# FDC.net
KiCad netlist of a schematic drawn in Altium Designer
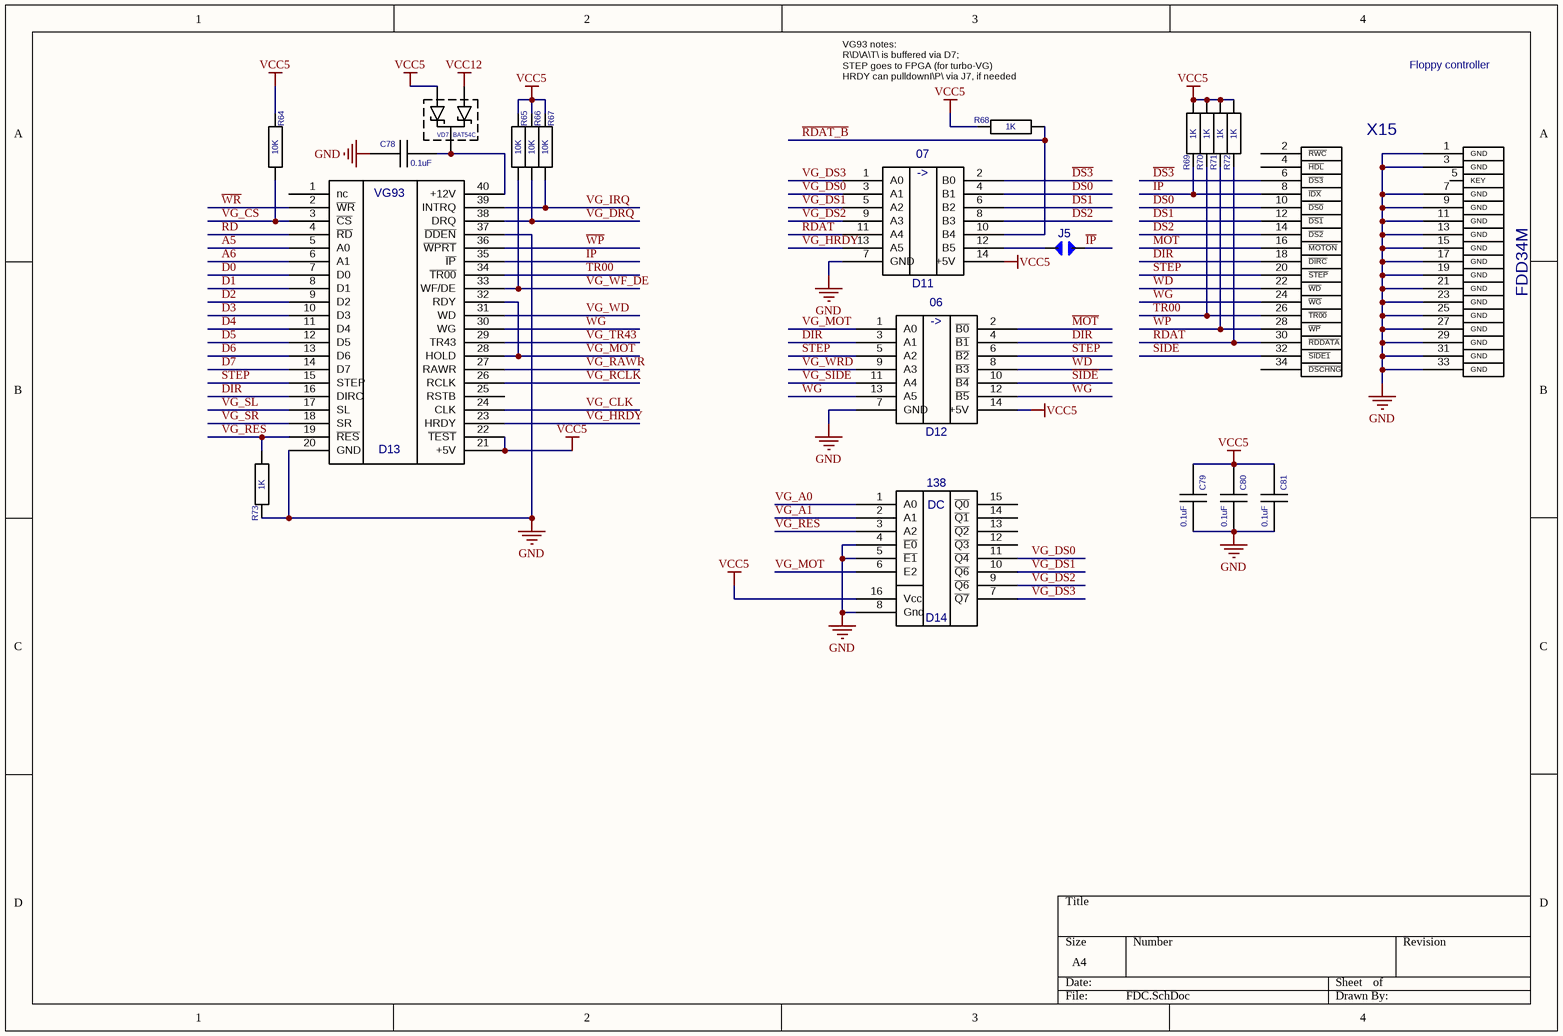
[diagram p0: FDC.SchDoc]

(export (version "E")
  (design (tool "Eeschema 10.0.6"))
  (components
    (comp (ref "C78")
      (value "0.1uF")
      (footprint "C-CHIP")
      (description "CAPCHIP")
      (libsource (lib "*") (part "CAPCHIP"))
    )
    (comp (ref "C79")
      (value "0.1uF")
      (footprint "C-CHIP")
      (description "CAPCHIP")
      (libsource (lib "*") (part "CAPCHIP"))
    )
    (comp (ref "C80")
      (value "0.1uF")
      (footprint "C-CHIP")
      (description "CAPCHIP")
      (libsource (lib "*") (part "CAPCHIP"))
    )
    (comp (ref "C81")
      (value "0.1uF")
      (footprint "C-CHIP")
      (description "CAPCHIP")
      (libsource (lib "*") (part "CAPCHIP"))
    )
    (comp (ref "D11") (value "07") (footprint "SO14") (libsource (lib "*") (part "07")))
    (comp (ref "D12") (value "06") (footprint "SO14") (libsource (lib "*") (part "06")))
    (comp (ref "D13") (value "KR1818VG93") (footprint "DIP40") (libsource (lib "*") (part "KR1818VG93")))
    (comp (ref "D14") (value "138") (footprint "SO16") (libsource (lib "*") (part "138")))
    (comp (ref "J5")
      (value "JUMPER")
      (footprint "JUMPER")
      (description "HLT->~IP")
      (libsource (lib "*") (part "JUMPER"))
    )
    (comp (ref "R64")
      (value "10K")
      (footprint "R-CHIP")
      (description "RESCHIP")
      (libsource (lib "*") (part "RESCHIP"))
    )
    (comp (ref "R65")
      (value "10K")
      (footprint "R-CHIP")
      (description "RESCHIP")
      (libsource (lib "*") (part "RESCHIP"))
    )
    (comp (ref "R66")
      (value "10K")
      (footprint "R-CHIP")
      (description "RESCHIP")
      (libsource (lib "*") (part "RESCHIP"))
    )
    (comp (ref "R67")
      (value "10K")
      (footprint "R-CHIP")
      (description "RESCHIP")
      (libsource (lib "*") (part "RESCHIP"))
    )
    (comp (ref "R68")
      (value "1K")
      (footprint "R-CHIP")
      (description "RESCHIP")
      (libsource (lib "*") (part "RESCHIP"))
    )
    (comp (ref "R69")
      (value "1K")
      (footprint "R-CHIP")
      (description "RESCHIP")
      (libsource (lib "*") (part "RESCHIP"))
    )
    (comp (ref "R70")
      (value "1K")
      (footprint "R-CHIP")
      (description "RESCHIP")
      (libsource (lib "*") (part "RESCHIP"))
    )
    (comp (ref "R71")
      (value "1K")
      (footprint "R-CHIP")
      (description "RESCHIP")
      (libsource (lib "*") (part "RESCHIP"))
    )
    (comp (ref "R72")
      (value "1K")
      (footprint "R-CHIP")
      (description "RESCHIP")
      (libsource (lib "*") (part "RESCHIP"))
    )
    (comp (ref "R73")
      (value "1K")
      (footprint "R-CHIP")
      (description "RESCHIP")
      (libsource (lib "*") (part "RESCHIP"))
    )
    (comp (ref "VD7") (value "BAT54C") (footprint "SOT-23") (libsource (lib "*") (part "BAT54C")))
    (comp (ref "X15") (value "FDD34M") (footprint "FDD34M") (libsource (lib "*") (part "FDD34M")))
  )
  (nets
    (net (code "1") (name "/A5") (class "Default")
      (node (ref "D13") (pin "5") (pinfunction "A0_5") (pintype "passive"))
    )
    (net (code "2") (name "/A6") (class "Default")
      (node (ref "D13") (pin "6") (pinfunction "A1_6") (pintype "passive"))
    )
    (net (code "3") (name "/D0") (class "Default")
      (node (ref "D13") (pin "7") (pinfunction "D0_7") (pintype "passive"))
    )
    (net (code "4") (name "/D1") (class "Default")
      (node (ref "D13") (pin "8") (pinfunction "D1_8") (pintype "passive"))
    )
    (net (code "5") (name "/D2") (class "Default")
      (node (ref "D13") (pin "9") (pinfunction "D2_9") (pintype "passive"))
    )
    (net (code "6") (name "/D3") (class "Default")
      (node (ref "D13") (pin "10") (pinfunction "D3_10") (pintype "passive"))
    )
    (net (code "7") (name "/D4") (class "Default")
      (node (ref "D13") (pin "11") (pinfunction "D4_11") (pintype "passive"))
    )
    (net (code "8") (name "/D5") (class "Default")
      (node (ref "D13") (pin "12") (pinfunction "D5_12") (pintype "passive"))
    )
    (net (code "9") (name "/D6") (class "Default")
      (node (ref "D13") (pin "13") (pinfunction "D6_13") (pintype "passive"))
    )
    (net (code "10") (name "/D7") (class "Default")
      (node (ref "D13") (pin "14") (pinfunction "D7_14") (pintype "passive"))
    )
    (net (code "11") (name "/DIR") (class "Default")
      (node (ref "D12") (pin "3") (pinfunction "A1_3") (pintype "passive"))
      (node (ref "D13") (pin "16") (pinfunction "DIRC_16") (pintype "passive"))
    )
    (net (code "12") (name "/STEP") (class "Default")
      (node (ref "D12") (pin "5") (pinfunction "A2_5") (pintype "passive"))
      (node (ref "D13") (pin "15") (pinfunction "STEP_15") (pintype "passive"))
    )
    (net (code "13") (name "/VG_A0") (class "Default")
      (node (ref "D14") (pin "1") (pinfunction "A0_1") (pintype "passive"))
    )
    (net (code "14") (name "/VG_A1") (class "Default")
      (node (ref "D14") (pin "2") (pinfunction "A1_2") (pintype "passive"))
    )
    (net (code "15") (name "/VG_CLK") (class "Default")
      (node (ref "D13") (pin "24") (pinfunction "CLK_24") (pintype "passive"))
    )
    (net (code "16") (name "/VG_DRQ") (class "Default")
      (node (ref "D13") (pin "38") (pinfunction "DRQ_38") (pintype "passive"))
      (node (ref "R66") (pin "1") (pinfunction "i/o_1") (pintype "passive"))
    )
    (net (code "17") (name "/VG_DS0") (class "Default")
      (node (ref "D11") (pin "3") (pinfunction "A1_3") (pintype "passive"))
      (node (ref "D14") (pin "11") (pinfunction "~{Q4}_11") (pintype "passive"))
    )
    (net (code "18") (name "/VG_DS1") (class "Default")
      (node (ref "D11") (pin "5") (pinfunction "A2_5") (pintype "passive"))
      (node (ref "D14") (pin "10") (pinfunction "~{Q6}_10") (pintype "passive"))
    )
    (net (code "19") (name "/VG_DS2") (class "Default")
      (node (ref "D11") (pin "9") (pinfunction "A3_9") (pintype "passive"))
      (node (ref "D14") (pin "9") (pinfunction "~{Q6}_9") (pintype "passive"))
    )
    (net (code "20") (name "/VG_DS3") (class "Default")
      (node (ref "D11") (pin "1") (pinfunction "A0_1") (pintype "passive"))
      (node (ref "D14") (pin "7") (pinfunction "~{Q7}_7") (pintype "passive"))
    )
    (net (code "21") (name "/VG_HRDY") (class "Default")
      (node (ref "D11") (pin "13") (pinfunction "A5_13") (pintype "passive"))
      (node (ref "D13") (pin "23") (pinfunction "HRDY_23") (pintype "passive"))
    )
    (net (code "22") (name "/VG_IRQ") (class "Default")
      (node (ref "D13") (pin "39") (pinfunction "INTRQ_39") (pintype "passive"))
      (node (ref "R67") (pin "1") (pinfunction "i/o_1") (pintype "passive"))
    )
    (net (code "23") (name "/VG_MOT") (class "Default")
      (node (ref "D12") (pin "1") (pinfunction "A0_1") (pintype "passive"))
      (node (ref "D13") (pin "28") (pinfunction "HOLD_28") (pintype "passive"))
      (node (ref "D13") (pin "32") (pinfunction "RDY_32") (pintype "passive"))
      (node (ref "D14") (pin "6") (pinfunction "E2_6") (pintype "passive"))
    )
    (net (code "24") (name "/VG_RAWR") (class "Default")
      (node (ref "D13") (pin "27") (pinfunction "RAWR_27") (pintype "passive"))
    )
    (net (code "25") (name "/VG_RCLK") (class "Default")
      (node (ref "D13") (pin "26") (pinfunction "RCLK_26") (pintype "passive"))
    )
    (net (code "26") (name "/VG_SIDE") (class "Default")
      (node (ref "D12") (pin "11") (pinfunction "A4_11") (pintype "passive"))
    )
    (net (code "27") (name "/VG_SL") (class "Default")
      (node (ref "D13") (pin "17") (pinfunction "SL_17") (pintype "passive"))
    )
    (net (code "28") (name "/VG_SR") (class "Default")
      (node (ref "D13") (pin "18") (pinfunction "SR_18") (pintype "passive"))
    )
    (net (code "29") (name "/VG_TR43") (class "Default")
      (node (ref "D13") (pin "29") (pinfunction "TR43_29") (pintype "passive"))
    )
    (net (code "30") (name "/VG_WD") (class "Default")
      (node (ref "D13") (pin "31") (pinfunction "WD_31") (pintype "passive"))
    )
    (net (code "31") (name "/VG_WF_DE") (class "Default")
      (node (ref "D13") (pin "33") (pinfunction "WF/DE_33") (pintype "passive"))
      (node (ref "R65") (pin "1") (pinfunction "i/o_1") (pintype "passive"))
    )
    (net (code "32") (name "/VG_WRD") (class "Default")
      (node (ref "D12") (pin "9") (pinfunction "A3_9") (pintype "passive"))
    )
    (net (code "33") (name "/WG") (class "Default")
      (node (ref "D12") (pin "13") (pinfunction "A5_13") (pintype "passive"))
      (node (ref "D13") (pin "30") (pinfunction "WG_30") (pintype "passive"))
    )
    (net (code "34") (name "/~{DIR}") (class "Default")
      (node (ref "D12") (pin "4") (pinfunction "~{B1}_4") (pintype "passive"))
      (node (ref "X15") (pin "18") (pinfunction "~{DIRC}_18") (pintype "passive"))
    )
    (net (code "35") (name "/~{DS0}") (class "Default")
      (node (ref "D11") (pin "4") (pinfunction "B1_4") (pintype "passive"))
      (node (ref "X15") (pin "10") (pinfunction "~{DS0}_10") (pintype "passive"))
    )
    (net (code "36") (name "/~{DS1}") (class "Default")
      (node (ref "D11") (pin "6") (pinfunction "B2_6") (pintype "passive"))
      (node (ref "X15") (pin "12") (pinfunction "~{DS1}_12") (pintype "passive"))
    )
    (net (code "37") (name "/~{DS2}") (class "Default")
      (node (ref "D11") (pin "8") (pinfunction "B3_8") (pintype "passive"))
      (node (ref "X15") (pin "14") (pinfunction "~{DS2}_14") (pintype "passive"))
    )
    (net (code "38") (name "/~{DS3}") (class "Default")
      (node (ref "D11") (pin "2") (pinfunction "B0_2") (pintype "passive"))
      (node (ref "X15") (pin "6") (pinfunction "~{DS3}_6") (pintype "passive"))
    )
    (net (code "39") (name "/~{IP}") (class "Default")
      (node (ref "D13") (pin "35") (pinfunction "~{IP}_35") (pintype "passive"))
      (node (ref "J5") (pin "1") (pinfunction "2_1") (pintype "passive"))
      (node (ref "R69") (pin "2") (pinfunction "i/o1_2") (pintype "passive"))
      (node (ref "X15") (pin "8") (pinfunction "~{IDX}_8") (pintype "passive"))
    )
    (net (code "40") (name "/~{MOT}") (class "Default")
      (node (ref "D12") (pin "2") (pinfunction "~{B0}_2") (pintype "passive"))
      (node (ref "X15") (pin "16") (pinfunction "~{MOTON}_16") (pintype "passive"))
    )
    (net (code "41") (name "/~{RDAT_B}") (class "Default")
      (node (ref "D11") (pin "10") (pinfunction "B4_10") (pintype "passive"))
      (node (ref "R68") (pin "1") (pinfunction "i/o_1") (pintype "passive"))
    )
    (net (code "42") (name "/~{RDAT}") (class "Default")
      (node (ref "D11") (pin "11") (pinfunction "A4_11") (pintype "passive"))
      (node (ref "R72") (pin "2") (pinfunction "i/o1_2") (pintype "passive"))
      (node (ref "X15") (pin "30") (pinfunction "~{RDDATA}_30") (pintype "passive"))
    )
    (net (code "43") (name "/~{RD}") (class "Default")
      (node (ref "D13") (pin "4") (pinfunction "~{RD}_4") (pintype "passive"))
    )
    (net (code "44") (name "/~{SIDE}") (class "Default")
      (node (ref "D12") (pin "10") (pinfunction "~{B4}_10") (pintype "passive"))
      (node (ref "X15") (pin "32") (pinfunction "~{SIDE1}_32") (pintype "passive"))
    )
    (net (code "45") (name "/~{STEP}") (class "Default")
      (node (ref "D12") (pin "6") (pinfunction "~{B2}_6") (pintype "passive"))
      (node (ref "X15") (pin "20") (pinfunction "~{STEP}_20") (pintype "passive"))
    )
    (net (code "46") (name "/~{TR00}") (class "Default")
      (node (ref "D13") (pin "34") (pinfunction "~{TR00}_34") (pintype "passive"))
      (node (ref "R70") (pin "2") (pinfunction "i/o1_2") (pintype "passive"))
      (node (ref "X15") (pin "26") (pinfunction "~{TR00}_26") (pintype "passive"))
    )
    (net (code "47") (name "/~{VG_CS}") (class "Default")
      (node (ref "D13") (pin "3") (pinfunction "~{CS}_3") (pintype "passive"))
      (node (ref "R64") (pin "1") (pinfunction "i/o_1") (pintype "passive"))
    )
    (net (code "48") (name "/~{VG_RES}") (class "Default")
      (node (ref "D13") (pin "19") (pinfunction "~{RES}_19") (pintype "passive"))
      (node (ref "D14") (pin "3") (pinfunction "A2_3") (pintype "passive"))
      (node (ref "R73") (pin "1") (pinfunction "i/o_1") (pintype "passive"))
    )
    (net (code "49") (name "/~{WD}") (class "Default")
      (node (ref "D12") (pin "8") (pinfunction "~{B3}_8") (pintype "passive"))
      (node (ref "X15") (pin "22") (pinfunction "~{WD}_22") (pintype "passive"))
    )
    (net (code "50") (name "/~{WG}") (class "Default")
      (node (ref "D12") (pin "12") (pinfunction "~{B5}_12") (pintype "passive"))
      (node (ref "X15") (pin "24") (pinfunction "~{WG}_24") (pintype "passive"))
    )
    (net (code "51") (name "/~{WP}") (class "Default")
      (node (ref "D13") (pin "36") (pinfunction "~{WPRT}_36") (pintype "passive"))
      (node (ref "R71") (pin "2") (pinfunction "i/o1_2") (pintype "passive"))
      (node (ref "X15") (pin "28") (pinfunction "~{WP}_28") (pintype "passive"))
    )
    (net (code "52") (name "/~{WR}") (class "Default")
      (node (ref "D13") (pin "2") (pinfunction "~{WR}_2") (pintype "passive"))
    )
    (net (code "53") (name "GND") (class "Default")
      (node (ref "C78") (pin "1") (pinfunction "1_1") (pintype "passive"))
      (node (ref "C79") (pin "2") (pinfunction "2_2") (pintype "passive"))
      (node (ref "C80") (pin "2") (pinfunction "2_2") (pintype "passive"))
      (node (ref "C81") (pin "2") (pinfunction "2_2") (pintype "passive"))
      (node (ref "D11") (pin "7") (pinfunction "GND_7") (pintype "passive"))
      (node (ref "D12") (pin "7") (pinfunction "GND_7") (pintype "passive"))
      (node (ref "D13") (pin "20") (pinfunction "GND_20") (pintype "passive"))
      (node (ref "D13") (pin "37") (pinfunction "~{DDEN}_37") (pintype "passive"))
      (node (ref "D14") (pin "4") (pinfunction "~{E0}_4") (pintype "passive"))
      (node (ref "D14") (pin "5") (pinfunction "~{E1}_5") (pintype "passive"))
      (node (ref "D14") (pin "8") (pinfunction "Gnd_8") (pintype "passive"))
      (node (ref "R73") (pin "2") (pinfunction "i/o1_2") (pintype "passive"))
      (node (ref "X15") (pin "1") (pinfunction "GND_1") (pintype "passive"))
      (node (ref "X15") (pin "11") (pinfunction "GND_11") (pintype "passive"))
      (node (ref "X15") (pin "13") (pinfunction "GND_13") (pintype "passive"))
      (node (ref "X15") (pin "15") (pinfunction "GND_15") (pintype "passive"))
      (node (ref "X15") (pin "17") (pinfunction "GND_17") (pintype "passive"))
      (node (ref "X15") (pin "19") (pinfunction "GND_19") (pintype "passive"))
      (node (ref "X15") (pin "21") (pinfunction "GND_21") (pintype "passive"))
      (node (ref "X15") (pin "23") (pinfunction "GND_23") (pintype "passive"))
      (node (ref "X15") (pin "25") (pinfunction "GND_25") (pintype "passive"))
      (node (ref "X15") (pin "27") (pinfunction "GND_27") (pintype "passive"))
      (node (ref "X15") (pin "29") (pinfunction "GND_29") (pintype "passive"))
      (node (ref "X15") (pin "3") (pinfunction "GND_3") (pintype "passive"))
      (node (ref "X15") (pin "31") (pinfunction "GND_31") (pintype "passive"))
      (node (ref "X15") (pin "33") (pinfunction "GND_33") (pintype "passive"))
      (node (ref "X15") (pin "7") (pinfunction "GND_7") (pintype "passive"))
      (node (ref "X15") (pin "9") (pinfunction "GND_9") (pintype "passive"))
    )
    (net (code "54") (name "Net-(D11-B5)") (class "Default")
      (node (ref "D11") (pin "12") (pinfunction "B5_12") (pintype "passive"))
      (node (ref "J5") (pin "0") (pinfunction "1_0") (pintype "passive"))
    )
    (net (code "55") (name "Net-(D13-+12V)") (class "Default")
      (node (ref "C78") (pin "2") (pinfunction "2_2") (pintype "passive"))
      (node (ref "D13") (pin "40") (pinfunction "+12V_40") (pintype "passive"))
      (node (ref "VD7") (pin "3") (pinfunction "3_3") (pintype "passive"))
    )
    (net (code "56") (name "VCC5") (class "Default")
      (node (ref "C79") (pin "1") (pinfunction "1_1") (pintype "passive"))
      (node (ref "C80") (pin "1") (pinfunction "1_1") (pintype "passive"))
      (node (ref "C81") (pin "1") (pinfunction "1_1") (pintype "passive"))
      (node (ref "D11") (pin "14") (pinfunction "+5V_14") (pintype "passive"))
      (node (ref "D12") (pin "14") (pinfunction "+5V_14") (pintype "passive"))
      (node (ref "D13") (pin "21") (pinfunction "+5V_21") (pintype "passive"))
      (node (ref "D13") (pin "22") (pinfunction "~{TEST}_22") (pintype "passive"))
      (node (ref "D14") (pin "16") (pinfunction "Vcc_16") (pintype "passive"))
      (node (ref "R64") (pin "2") (pinfunction "i/o1_2") (pintype "passive"))
      (node (ref "R65") (pin "2") (pinfunction "i/o1_2") (pintype "passive"))
      (node (ref "R66") (pin "2") (pinfunction "i/o1_2") (pintype "passive"))
      (node (ref "R67") (pin "2") (pinfunction "i/o1_2") (pintype "passive"))
      (node (ref "R68") (pin "2") (pinfunction "i/o1_2") (pintype "passive"))
      (node (ref "R69") (pin "1") (pinfunction "i/o_1") (pintype "passive"))
      (node (ref "R70") (pin "1") (pinfunction "i/o_1") (pintype "passive"))
      (node (ref "R71") (pin "1") (pinfunction "i/o_1") (pintype "passive"))
      (node (ref "R72") (pin "1") (pinfunction "i/o_1") (pintype "passive"))
      (node (ref "VD7") (pin "2") (pinfunction "2_2") (pintype "passive"))
    )
    (net (code "57") (name "VCC12") (class "Default")
      (node (ref "VD7") (pin "1") (pinfunction "1_1") (pintype "passive"))
    )
    (net (code "58") (name "unconnected-(D13-RSTB-Pad25)") (class "Default")
      (node (ref "D13") (pin "25") (pinfunction "RSTB_25") (pintype "passive"))
    )
    (net (code "59") (name "unconnected-(D13-nc-Pad1)") (class "Default")
      (node (ref "D13") (pin "1") (pinfunction "nc_1") (pintype "passive"))
    )
    (net (code "60") (name "unconnected-(D14-~{Q0}-Pad15)") (class "Default")
      (node (ref "D14") (pin "15") (pinfunction "~{Q0}_15") (pintype "passive"))
    )
    (net (code "61") (name "unconnected-(D14-~{Q1}-Pad14)") (class "Default")
      (node (ref "D14") (pin "14") (pinfunction "~{Q1}_14") (pintype "passive"))
    )
    (net (code "62") (name "unconnected-(D14-~{Q2}-Pad13)") (class "Default")
      (node (ref "D14") (pin "13") (pinfunction "~{Q2}_13") (pintype "passive"))
    )
    (net (code "63") (name "unconnected-(D14-~{Q3}-Pad12)") (class "Default")
      (node (ref "D14") (pin "12") (pinfunction "~{Q3}_12") (pintype "passive"))
    )
    (net (code "64") (name "unconnected-(X15-KEY-Pad5)") (class "Default")
      (node (ref "X15") (pin "5") (pinfunction "KEY_5") (pintype "passive"))
    )
    (net (code "65") (name "unconnected-(X15-~{DSCHNG}-Pad34)") (class "Default")
      (node (ref "X15") (pin "34") (pinfunction "~{DSCHNG}_34") (pintype "passive"))
    )
    (net (code "66") (name "unconnected-(X15-~{HDL}-Pad4)") (class "Default")
      (node (ref "X15") (pin "4") (pinfunction "~{HDL}_4") (pintype "passive"))
    )
    (net (code "67") (name "unconnected-(X15-~{RWC}-Pad2)") (class "Default")
      (node (ref "X15") (pin "2") (pinfunction "~{RWC}_2") (pintype "passive"))
    )
  )
)
